# inktime.net
KiCad netlist of a schematic drawn in EAGLE
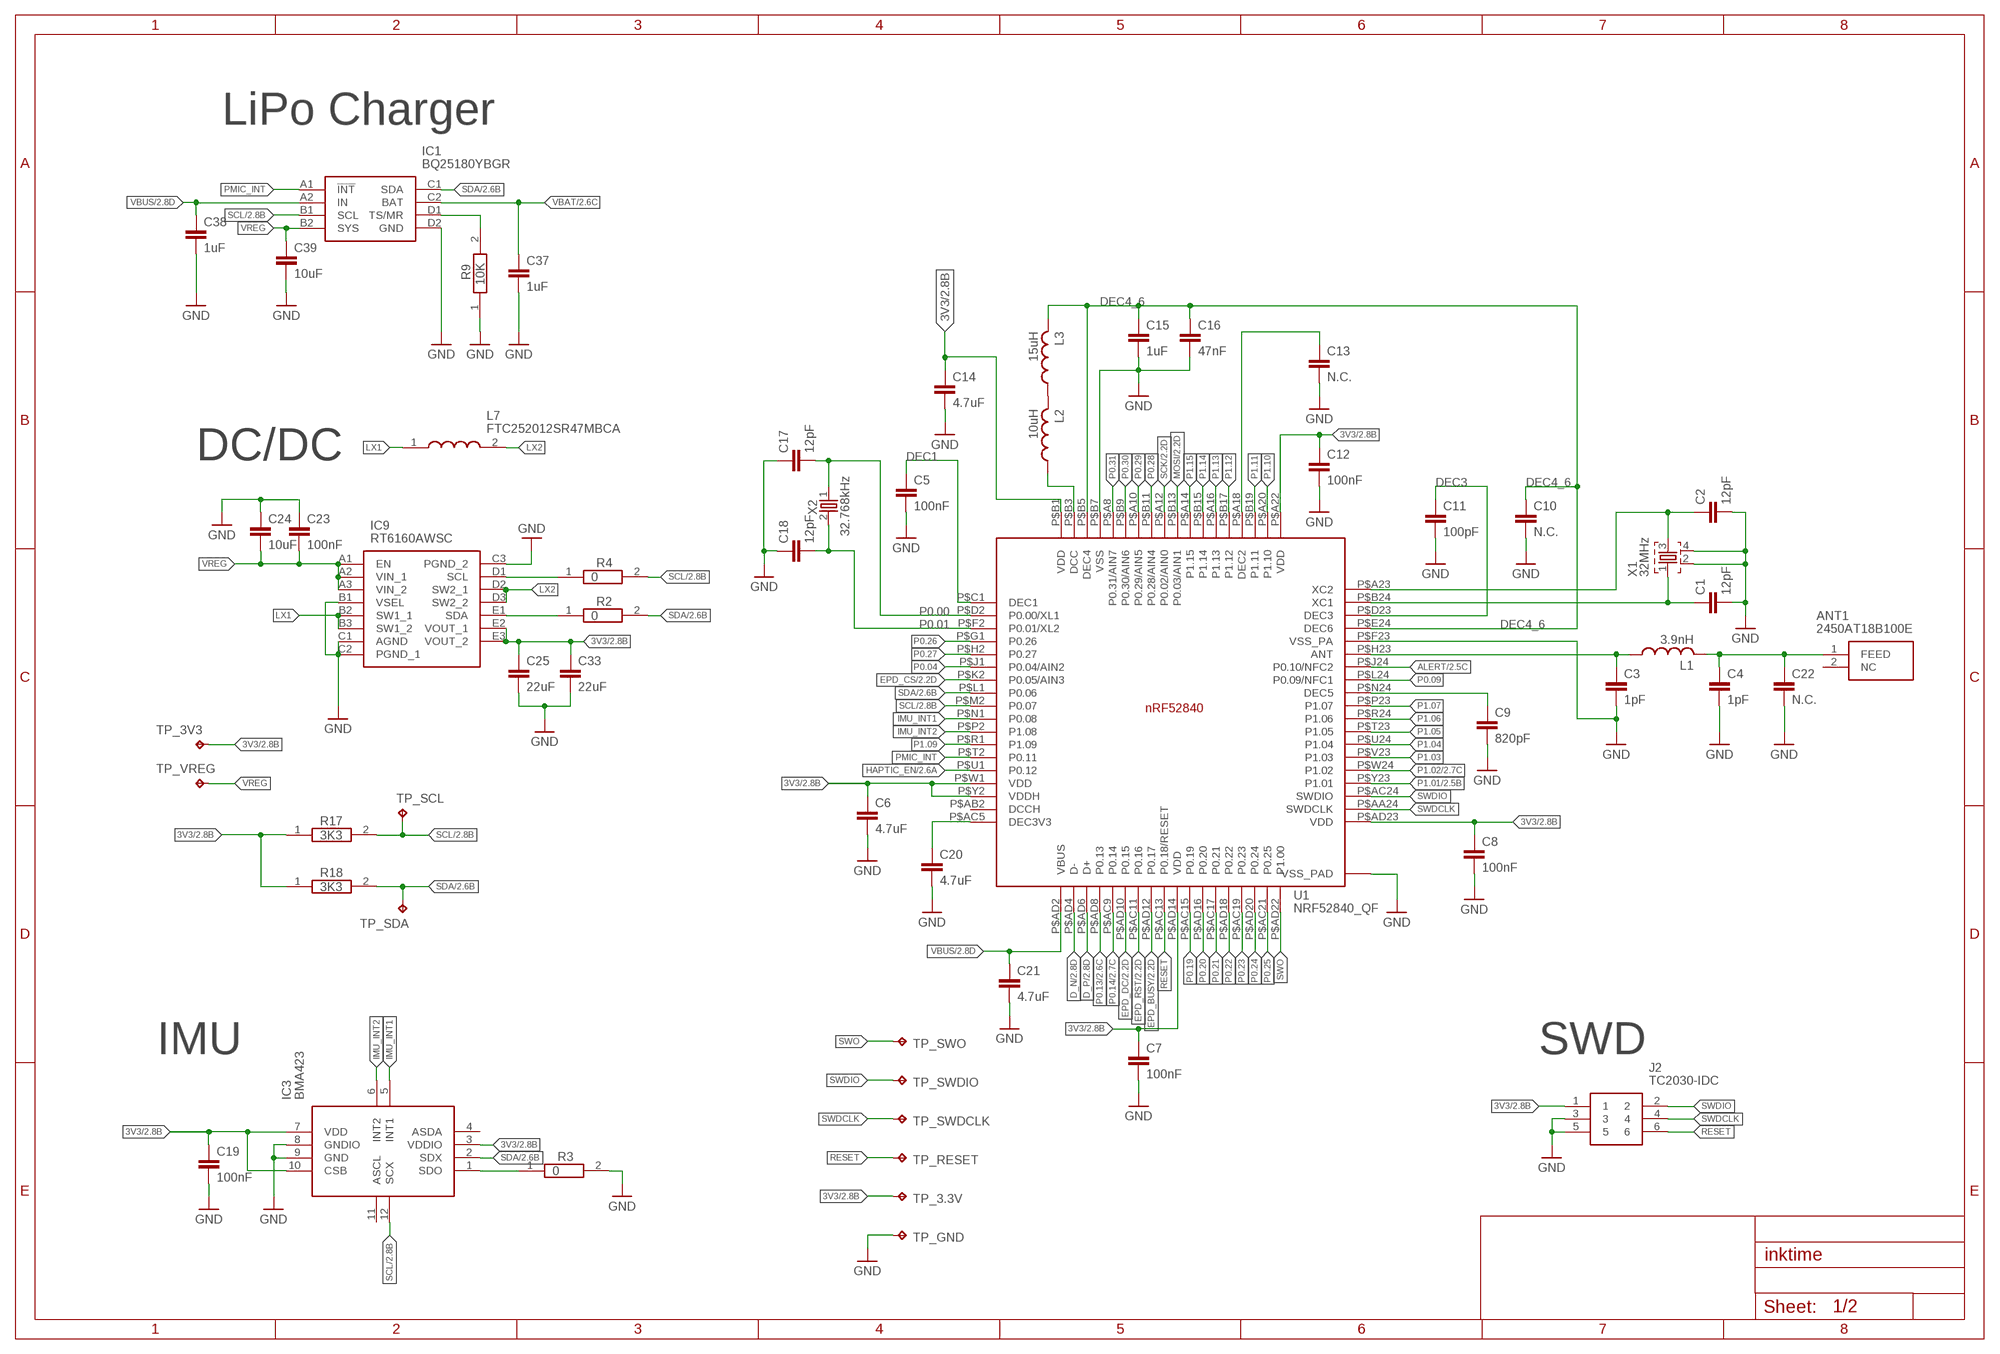
[diagram p0: schematic, sheet 1]
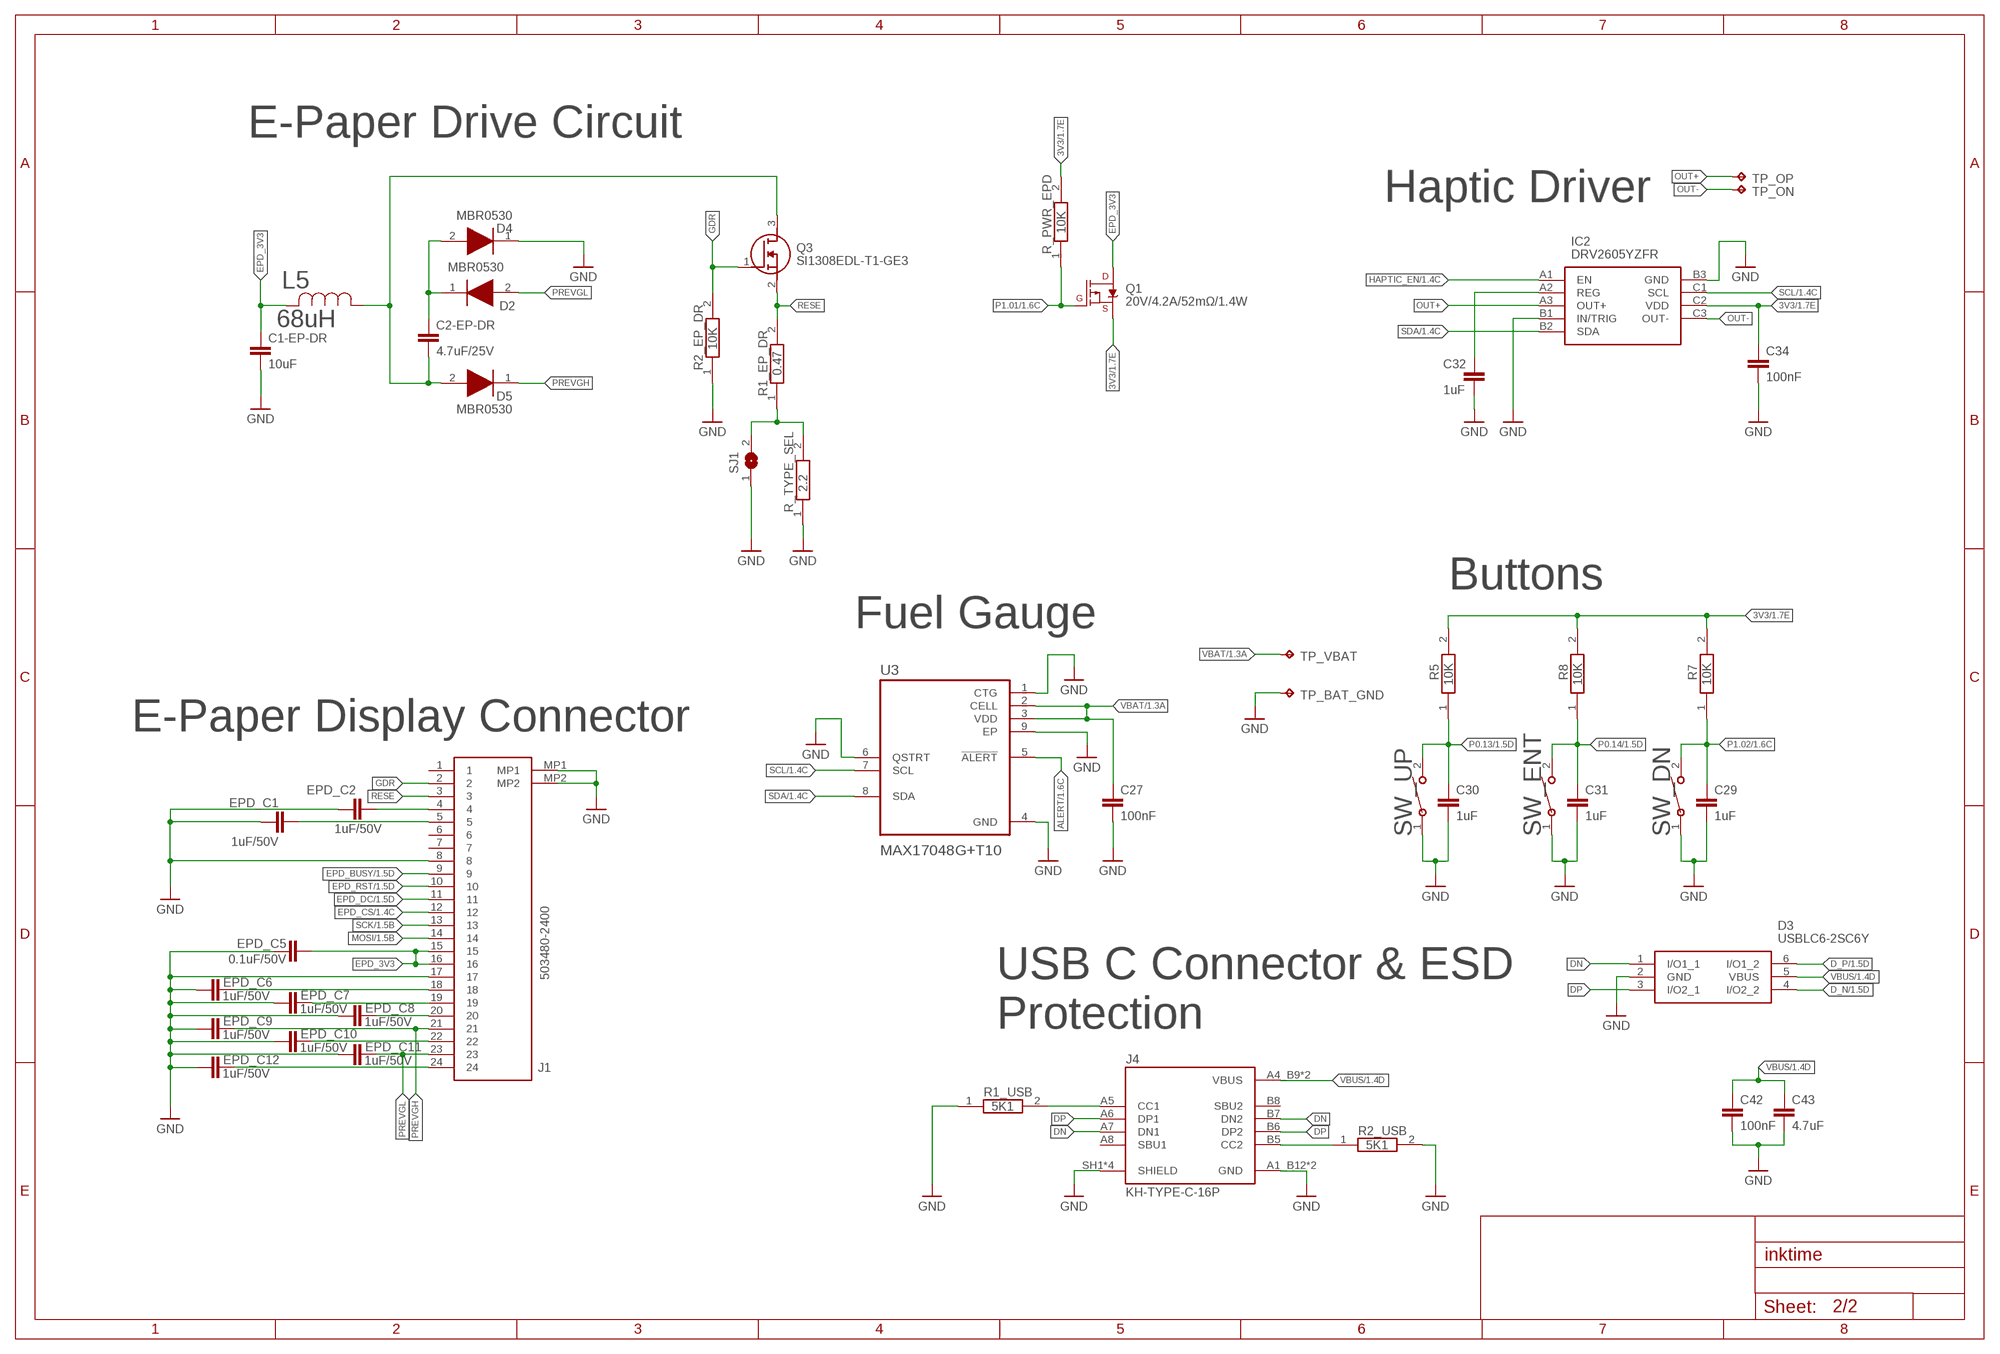
[diagram p1: schematic, sheet 2]

(export (version "E")
  (design (tool "Eeschema 10.0.6"))
  (components
    (comp (ref "C1-EP-DR")
      (value "10uF")
      (footprint "eagle-import:NORDIC_NRF_3_RESC0402_L")
      (libsource (lib "eagle-import") (part "NORDIC_NRF_3_CAPACITOR_0402_L"))
    )
    (comp (ref "C2-EP-DR")
      (value "4.7uF/25V")
      (footprint "eagle-import:NORDIC_NRF_3_RESC0402_L")
      (libsource (lib "eagle-import") (part "NORDIC_NRF_3_CAPACITOR_0402_L"))
    )
    (comp (ref "C27")
      (value "100nF")
      (footprint "eagle-import:NORDIC_NRF_3_RESC0201_L")
      (libsource (lib "eagle-import") (part "NORDIC_NRF_3_CAPACITOR_0201_L"))
    )
    (comp (ref "C29")
      (value "1uF")
      (footprint "eagle-import:NORDIC_NRF_3_RESC0402_L")
      (libsource (lib "eagle-import") (part "NORDIC_NRF_3_CAPACITOR_0402_L"))
    )
    (comp (ref "C30")
      (value "1uF")
      (footprint "eagle-import:NORDIC_NRF_3_RESC0402_L")
      (libsource (lib "eagle-import") (part "NORDIC_NRF_3_CAPACITOR_0402_L"))
    )
    (comp (ref "C31")
      (value "1uF")
      (footprint "eagle-import:NORDIC_NRF_3_RESC0402_L")
      (libsource (lib "eagle-import") (part "NORDIC_NRF_3_CAPACITOR_0402_L"))
    )
    (comp (ref "C32")
      (value "1uF")
      (footprint "eagle-import:NORDIC_NRF_3_RESC0402_L")
      (libsource (lib "eagle-import") (part "NORDIC_NRF_3_CAPACITOR_0402_L"))
    )
    (comp (ref "C34")
      (value "100nF")
      (footprint "eagle-import:NORDIC_NRF_3_RESC0201_L")
      (libsource (lib "eagle-import") (part "NORDIC_NRF_3_CAPACITOR_0201_L"))
    )
    (comp (ref "C42")
      (value "100nF")
      (footprint "eagle-import:NORDIC_NRF_3_RESC0201_L")
      (libsource (lib "eagle-import") (part "NORDIC_NRF_3_CAPACITOR_0201_L"))
    )
    (comp (ref "C43")
      (value "4.7uF")
      (footprint "eagle-import:NORDIC_NRF_3_RESC0402_L")
      (libsource (lib "eagle-import") (part "NORDIC_NRF_3_CAPACITOR_0402_L"))
    )
    (comp (ref "D2")
      (value "MBR0530")
      (footprint "eagle-import:ESP32_C6_LIBRARY_5_SOD3716X135N")
      (libsource (lib "eagle-import") (part "ESP32_C6_LIBRARY_5_MBR0530SOD"))
    )
    (comp (ref "D3")
      (value "USBLC6-2SC6Y")
      (footprint "eagle-import:ESP32_C6_LIBRARY_3_SOT95P280X145-6N")
      (fields (field (name "MF") "STMicroelectronics"))
      (libsource (lib "eagle-import") (part "ESP32_C6_LIBRARY_3_USBLC6-2SC6Y"))
    )
    (comp (ref "D4")
      (value "MBR0530")
      (footprint "eagle-import:ESP32_C6_LIBRARY_5_SOD3716X135N")
      (libsource (lib "eagle-import") (part "ESP32_C6_LIBRARY_5_MBR0530SOD"))
    )
    (comp (ref "D5")
      (value "MBR0530")
      (footprint "eagle-import:ESP32_C6_LIBRARY_5_SOD3716X135N")
      (libsource (lib "eagle-import") (part "ESP32_C6_LIBRARY_5_MBR0530SOD"))
    )
    (comp (ref "EPD_C1")
      (value "1uF/50V")
      (footprint "eagle-import:NORDIC_NRF_3_RESC0402_L")
      (libsource (lib "eagle-import") (part "NORDIC_NRF_3_CAPACITOR_0402_L"))
    )
    (comp (ref "EPD_C2")
      (value "1uF/50V")
      (footprint "eagle-import:NORDIC_NRF_3_RESC0402_L")
      (libsource (lib "eagle-import") (part "NORDIC_NRF_3_CAPACITOR_0402_L"))
    )
    (comp (ref "EPD_C5")
      (value "0.1uF/50V")
      (footprint "eagle-import:NORDIC_NRF_3_RESC0201_L")
      (libsource (lib "eagle-import") (part "NORDIC_NRF_3_CAPACITOR_0201_L"))
    )
    (comp (ref "EPD_C6")
      (value "1uF/50V")
      (footprint "eagle-import:NORDIC_NRF_3_RESC0402_L")
      (libsource (lib "eagle-import") (part "NORDIC_NRF_3_CAPACITOR_0402_L"))
    )
    (comp (ref "EPD_C7")
      (value "1uF/50V")
      (footprint "eagle-import:NORDIC_NRF_3_RESC0402_L")
      (libsource (lib "eagle-import") (part "NORDIC_NRF_3_CAPACITOR_0402_L"))
    )
    (comp (ref "EPD_C8")
      (value "1uF/50V")
      (footprint "eagle-import:NORDIC_NRF_3_RESC0402_L")
      (libsource (lib "eagle-import") (part "NORDIC_NRF_3_CAPACITOR_0402_L"))
    )
    (comp (ref "EPD_C9")
      (value "1uF/50V")
      (footprint "eagle-import:NORDIC_NRF_3_RESC0402_L")
      (libsource (lib "eagle-import") (part "NORDIC_NRF_3_CAPACITOR_0402_L"))
    )
    (comp (ref "EPD_C10")
      (value "1uF/50V")
      (footprint "eagle-import:NORDIC_NRF_3_RESC0402_L")
      (libsource (lib "eagle-import") (part "NORDIC_NRF_3_CAPACITOR_0402_L"))
    )
    (comp (ref "EPD_C11")
      (value "1uF/50V")
      (footprint "eagle-import:NORDIC_NRF_3_RESC0402_L")
      (libsource (lib "eagle-import") (part "NORDIC_NRF_3_CAPACITOR_0402_L"))
    )
    (comp (ref "EPD_C12")
      (value "1uF/50V")
      (footprint "eagle-import:NORDIC_NRF_3_RESC0402_L")
      (libsource (lib "eagle-import") (part "NORDIC_NRF_3_CAPACITOR_0402_L"))
    )
    (comp (ref "IC2")
      (value "DRV2605YZFR")
      (footprint "eagle-import:DRV2605YZFR_BGA9C50P3X3_144X144X62")
      (libsource (lib "eagle-import") (part "DRV2605YZFR_DRV2605YZFR"))
    )
    (comp (ref "J1")
      (value "503480-2400")
      (footprint "eagle-import:503480-2400_5034802400")
      (fields (field (name "MOUSER_PART_NUMBER") "538-503480-2400"))
      (libsource (lib "eagle-import") (part "503480-2400_503480-2400"))
    )
    (comp (ref "J4")
      (value "KH-TYPE-C-16P")
      (footprint "eagle-import:KH-TYPE-C-16P_KINGHELM_KH-TYPE-C-16P")
      (fields (field (name "MF") "kinghelm"))
      (libsource (lib "eagle-import") (part "KH-TYPE-C-16P_KH-TYPE-C-16P"))
    )
    (comp (ref "L5")
      (value "68uH")
      (footprint "eagle-import:ESP32_C6_LIBRARY_2_IND_4828-WE-TPC_WRE")
      (fields
        (field (name "MANUFACTURER_PART_NUMBER") "744043680")
        (field (name "COPYRIGHT") "Copyright (C) 2024 Ultra Librarian. All rights reserved.")
      )
      (libsource (lib "eagle-import") (part "ESP32_C6_LIBRARY_2_744043680IND_4828-WE-TPC_WRE"))
    )
    (comp (ref "Q1")
      (value "20V/4.2A/52mΩ/1.4W")
      (footprint "eagle-import:ESP32_C6_LIBRARY_4_ESP32_C6_LIBRARY_4_ESP32_C6_LIBRARY_4_ESP32_C6_LIBRARY_4_ESP32_WROVER_SPARKFUN-DISCRETESEMI_SOT23-3")
      (libsource (lib "eagle-import") (part "ESP32_C6_LIBRARY_4_ESP32_WROVER_SPARKFUN-DISCRETESEMI_MOSFET_PCH-DMG2305UX-7"))
    )
    (comp (ref "Q3")
      (value "SI1308EDL-T1-GE3")
      (footprint "eagle-import:ESP32_C6_LIBRARY_6_SOT65P210X110-3N")
      (fields (field (name "MF") "Vishay Siliconix"))
      (libsource (lib "eagle-import") (part "ESP32_C6_LIBRARY_6_SI1308EDL-T1-GE3"))
    )
    (comp (ref "R1_EP_DR")
      (value "0.47")
      (footprint "eagle-import:CPF0201D7K68C1_0201")
      (libsource (lib "eagle-import") (part "CPF0201D7K68C1_CPF0201D7K68C1"))
    )
    (comp (ref "R1_USB")
      (value "5K1")
      (footprint "eagle-import:CPF0201D7K68C1_0201")
      (libsource (lib "eagle-import") (part "CPF0201D7K68C1_CPF0201D7K68C1"))
    )
    (comp (ref "R2_EP_DR")
      (value "10K")
      (footprint "eagle-import:CPF0201D7K68C1_0201")
      (libsource (lib "eagle-import") (part "CPF0201D7K68C1_CPF0201D7K68C1"))
    )
    (comp (ref "R2_USB")
      (value "5K1")
      (footprint "eagle-import:CPF0201D7K68C1_0201")
      (libsource (lib "eagle-import") (part "CPF0201D7K68C1_CPF0201D7K68C1"))
    )
    (comp (ref "R5")
      (value "10K")
      (footprint "eagle-import:CPF0201D7K68C1_0201")
      (libsource (lib "eagle-import") (part "CPF0201D7K68C1_CPF0201D7K68C1"))
    )
    (comp (ref "R7")
      (value "10K")
      (footprint "eagle-import:CPF0201D7K68C1_0201")
      (libsource (lib "eagle-import") (part "CPF0201D7K68C1_CPF0201D7K68C1"))
    )
    (comp (ref "R8")
      (value "10K")
      (footprint "eagle-import:CPF0201D7K68C1_0201")
      (libsource (lib "eagle-import") (part "CPF0201D7K68C1_CPF0201D7K68C1"))
    )
    (comp (ref "R_PWR_EPD")
      (value "10K")
      (footprint "eagle-import:CPF0201D7K68C1_0201")
      (libsource (lib "eagle-import") (part "CPF0201D7K68C1_CPF0201D7K68C1"))
    )
    (comp (ref "R_TYPE_SEL")
      (value "2.2")
      (footprint "eagle-import:CPF0201D7K68C1_0201")
      (libsource (lib "eagle-import") (part "CPF0201D7K68C1_CPF0201D7K68C1"))
    )
    (comp (ref "SJ1")
      (value "ESP32_C6_LIBRARY_7_JUMPER_SJ")
      (footprint "eagle-import:ESP32_C6_LIBRARY_7_JUMPER_SJ")
      (libsource (lib "eagle-import") (part "ESP32_C6_LIBRARY_7_JUMPER_SJ"))
    )
    (comp (ref "SW_DN")
      (value "2025-10-22_07-23-44_LIBRARY_EVP-AKE31ASW_EVP-AKE31A_PAN")
      (footprint "eagle-import:2025-10-22_07-23-44_LIBRARY_SW_EVP-AKE31A_PAN")
      (fields
        (field (name "MANUFACTURER_PART_NUMBER") "EVP-AKE31A")
        (field (name "COPYRIGHT") "Copyright (C) 2025 Ultra Librarian. All rights reserved.")
      )
      (libsource (lib "eagle-import") (part "2025-10-22_07-23-44_LIBRARY_EVP-AKE31ASW_EVP-AKE31A_PAN"))
    )
    (comp (ref "SW_ENT")
      (value "2025-10-22_07-23-44_LIBRARY_EVP-AKE31ASW_EVP-AKE31A_PAN")
      (footprint "eagle-import:2025-10-22_07-23-44_LIBRARY_SW_EVP-AKE31A_PAN")
      (fields
        (field (name "MANUFACTURER_PART_NUMBER") "EVP-AKE31A")
        (field (name "COPYRIGHT") "Copyright (C) 2025 Ultra Librarian. All rights reserved.")
      )
      (libsource (lib "eagle-import") (part "2025-10-22_07-23-44_LIBRARY_EVP-AKE31ASW_EVP-AKE31A_PAN"))
    )
    (comp (ref "SW_UP")
      (value "2025-10-22_07-23-44_LIBRARY_EVP-AKE31ASW_EVP-AKE31A_PAN")
      (footprint "eagle-import:2025-10-22_07-23-44_LIBRARY_SW_EVP-AKE31A_PAN")
      (fields
        (field (name "MANUFACTURER_PART_NUMBER") "EVP-AKE31A")
        (field (name "COPYRIGHT") "Copyright (C) 2025 Ultra Librarian. All rights reserved.")
      )
      (libsource (lib "eagle-import") (part "2025-10-22_07-23-44_LIBRARY_EVP-AKE31ASW_EVP-AKE31A_PAN"))
    )
    (comp (ref "TP_BAT_GND")
      (value "HECTOR_WATCH_1_TPTP20R")
      (footprint "eagle-import:HECTOR_WATCH_1_TP20R")
      (libsource (lib "eagle-import") (part "HECTOR_WATCH_1_TPTP20R"))
    )
    (comp (ref "TP_ON")
      (value "HECTOR_WATCH_1_TPTP20R")
      (footprint "eagle-import:HECTOR_WATCH_1_TP20R")
      (libsource (lib "eagle-import") (part "HECTOR_WATCH_1_TPTP20R"))
    )
    (comp (ref "TP_OP")
      (value "HECTOR_WATCH_1_TPTP20R")
      (footprint "eagle-import:HECTOR_WATCH_1_TP20R")
      (libsource (lib "eagle-import") (part "HECTOR_WATCH_1_TPTP20R"))
    )
    (comp (ref "TP_VBAT")
      (value "HECTOR_WATCH_1_TPTP20R")
      (footprint "eagle-import:HECTOR_WATCH_1_TP20R")
      (libsource (lib "eagle-import") (part "HECTOR_WATCH_1_TPTP20R"))
    )
    (comp (ref "U3")
      (value "MAX17048G+T10")
      (footprint "eagle-import:ESP32_C6_LIBRARY_SON50P200X200X80-9N")
      (fields (field (name "MF") "Analog Devices"))
      (libsource (lib "eagle-import") (part "ESP32_C6_LIBRARY_MAX17048G+T10"))
    )
    (comp (ref "ANT1")
      (value "2450AT18B100E")
      (footprint "eagle-import:2450AT18B100E_ANTC3216X140N")
      (fields (field (name "MOUSER_PART_NUMBER") "609-2450AT18B100E"))
      (libsource (lib "eagle-import") (part "2450AT18B100E_2450AT18B100E"))
    )
    (comp (ref "C1")
      (value "12pF")
      (footprint "eagle-import:NORDIC_NRF_3_RESC0201_L")
      (libsource (lib "eagle-import") (part "NORDIC_NRF_3_CAPACITOR_0201_L"))
    )
    (comp (ref "C2")
      (value "12pF")
      (footprint "eagle-import:NORDIC_NRF_3_RESC0201_L")
      (libsource (lib "eagle-import") (part "NORDIC_NRF_3_CAPACITOR_0201_L"))
    )
    (comp (ref "C3")
      (value "1pF")
      (footprint "eagle-import:NORDIC_NRF_3_RESC0201_L")
      (libsource (lib "eagle-import") (part "NORDIC_NRF_3_CAPACITOR_0201_L"))
    )
    (comp (ref "C4")
      (value "1pF")
      (footprint "eagle-import:NORDIC_NRF_3_RESC0201_L")
      (libsource (lib "eagle-import") (part "NORDIC_NRF_3_CAPACITOR_0201_L"))
    )
    (comp (ref "C5")
      (value "100nF")
      (footprint "eagle-import:NORDIC_NRF_3_RESC0201_L")
      (libsource (lib "eagle-import") (part "NORDIC_NRF_3_CAPACITOR_0201_L"))
    )
    (comp (ref "C6")
      (value "4.7uF")
      (footprint "eagle-import:NORDIC_NRF_3_RESC0402_L")
      (libsource (lib "eagle-import") (part "NORDIC_NRF_3_CAPACITOR_0402_L"))
    )
    (comp (ref "C7")
      (value "100nF")
      (footprint "eagle-import:NORDIC_NRF_3_RESC0201_L")
      (libsource (lib "eagle-import") (part "NORDIC_NRF_3_CAPACITOR_0201_L"))
    )
    (comp (ref "C8")
      (value "100nF")
      (footprint "eagle-import:NORDIC_NRF_3_RESC0201_L")
      (libsource (lib "eagle-import") (part "NORDIC_NRF_3_CAPACITOR_0201_L"))
    )
    (comp (ref "C9")
      (value "820pF")
      (footprint "eagle-import:NORDIC_NRF_3_RESC0201_L")
      (libsource (lib "eagle-import") (part "NORDIC_NRF_3_CAPACITOR_0201_L"))
    )
    (comp (ref "C10")
      (value "N.C.")
      (footprint "eagle-import:NORDIC_NRF_3_RESC0201_L")
      (libsource (lib "eagle-import") (part "NORDIC_NRF_3_CAPACITOR_0201_L"))
    )
    (comp (ref "C11")
      (value "100pF")
      (footprint "eagle-import:NORDIC_NRF_3_RESC0201_L")
      (libsource (lib "eagle-import") (part "NORDIC_NRF_3_CAPACITOR_0201_L"))
    )
    (comp (ref "C12")
      (value "100nF")
      (footprint "eagle-import:NORDIC_NRF_3_RESC0201_L")
      (libsource (lib "eagle-import") (part "NORDIC_NRF_3_CAPACITOR_0201_L"))
    )
    (comp (ref "C13")
      (value "N.C.")
      (footprint "eagle-import:NORDIC_NRF_3_RESC0201_L")
      (libsource (lib "eagle-import") (part "NORDIC_NRF_3_CAPACITOR_0201_L"))
    )
    (comp (ref "C14")
      (value "4.7uF")
      (footprint "eagle-import:NORDIC_NRF_3_RESC0402_L")
      (libsource (lib "eagle-import") (part "NORDIC_NRF_3_CAPACITOR_0402_L"))
    )
    (comp (ref "C15")
      (value "1uF")
      (footprint "eagle-import:NORDIC_NRF_3_RESC0402_L")
      (libsource (lib "eagle-import") (part "NORDIC_NRF_3_CAPACITOR_0402_L"))
    )
    (comp (ref "C16")
      (value "47nF")
      (footprint "eagle-import:NORDIC_NRF_3_RESC0201_L")
      (libsource (lib "eagle-import") (part "NORDIC_NRF_3_CAPACITOR_0201_L"))
    )
    (comp (ref "C17")
      (value "12pF")
      (footprint "eagle-import:NORDIC_NRF_3_RESC0201_L")
      (libsource (lib "eagle-import") (part "NORDIC_NRF_3_CAPACITOR_0201_L"))
    )
    (comp (ref "C18")
      (value "12pF")
      (footprint "eagle-import:NORDIC_NRF_3_RESC0201_L")
      (libsource (lib "eagle-import") (part "NORDIC_NRF_3_CAPACITOR_0201_L"))
    )
    (comp (ref "C19")
      (value "100nF")
      (footprint "eagle-import:NORDIC_NRF_3_RESC0201_L")
      (libsource (lib "eagle-import") (part "NORDIC_NRF_3_CAPACITOR_0201_L"))
    )
    (comp (ref "C20")
      (value "4.7uF")
      (footprint "eagle-import:NORDIC_NRF_3_RESC0402_L")
      (libsource (lib "eagle-import") (part "NORDIC_NRF_3_CAPACITOR_0402_L"))
    )
    (comp (ref "C21")
      (value "4.7uF")
      (footprint "eagle-import:NORDIC_NRF_3_RESC0402_L")
      (libsource (lib "eagle-import") (part "NORDIC_NRF_3_CAPACITOR_0402_L"))
    )
    (comp (ref "C22")
      (value "N.C.")
      (footprint "eagle-import:NORDIC_NRF_3_RESC0201_L")
      (libsource (lib "eagle-import") (part "NORDIC_NRF_3_CAPACITOR_0201_L"))
    )
    (comp (ref "C23")
      (value "100nF")
      (footprint "eagle-import:NORDIC_NRF_3_RESC0201_L")
      (libsource (lib "eagle-import") (part "NORDIC_NRF_3_CAPACITOR_0201_L"))
    )
    (comp (ref "C24")
      (value "10uF")
      (footprint "eagle-import:NORDIC_NRF_3_RESC0402_L")
      (libsource (lib "eagle-import") (part "NORDIC_NRF_3_CAPACITOR_0402_L"))
    )
    (comp (ref "C25")
      (value "22uF")
      (footprint "eagle-import:NORDIC_NRF_3_RESC0402_L")
      (libsource (lib "eagle-import") (part "NORDIC_NRF_3_CAPACITOR_0402_L"))
    )
    (comp (ref "C33")
      (value "22uF")
      (footprint "eagle-import:NORDIC_NRF_3_RESC0402_L")
      (libsource (lib "eagle-import") (part "NORDIC_NRF_3_CAPACITOR_0402_L"))
    )
    (comp (ref "C37")
      (value "1uF")
      (footprint "eagle-import:NORDIC_NRF_3_RESC0402_L")
      (libsource (lib "eagle-import") (part "NORDIC_NRF_3_CAPACITOR_0402_L"))
    )
    (comp (ref "C38")
      (value "1uF")
      (footprint "eagle-import:NORDIC_NRF_3_RESC0402_L")
      (libsource (lib "eagle-import") (part "NORDIC_NRF_3_CAPACITOR_0402_L"))
    )
    (comp (ref "C39")
      (value "10uF")
      (footprint "eagle-import:NORDIC_NRF_3_RESC0402_L")
      (libsource (lib "eagle-import") (part "NORDIC_NRF_3_CAPACITOR_0402_L"))
    )
    (comp (ref "IC1")
      (value "BQ25180YBGR")
      (footprint "eagle-import:BQ25180YBGR_BGA8C40P2X4_100X155X50")
      (fields (field (name "MOUSER_PART_NUMBER") "595-BQ25180YBGR"))
      (libsource (lib "eagle-import") (part "BQ25180YBGR_BQ25180YBGR"))
    )
    (comp (ref "IC3")
      (value "BMA423")
      (footprint "eagle-import:BMA423_BMA423")
      (fields (field (name "MOUSER_PART_NUMBER") "262-BMA423"))
      (libsource (lib "eagle-import") (part "BMA423_BMA423"))
    )
    (comp (ref "IC9")
      (value "RT6160AWSC")
      (footprint "eagle-import:RT6160AWSC_BGA15C40P3X5_140X230X60")
      (fields (field (name "MOUSER_PART_NUMBER") "835-RT6160AWSC"))
      (libsource (lib "eagle-import") (part "RT6160AWSC_RT6160AWSC"))
    )
    (comp (ref "J2")
      (value "TC2030-IDC")
      (footprint "eagle-import:TC2030-IDC_TC2030IDC")
      (libsource (lib "eagle-import") (part "TC2030-IDC_TC2030-IDC"))
    )
    (comp (ref "L1")
      (value "3.9nH")
      (footprint "eagle-import:NORDIC_NRF_2_RESC0402_L")
      (libsource (lib "eagle-import") (part "NORDIC_NRF_2_INDUCTOR_0402_L"))
    )
    (comp (ref "L2")
      (value "10uH")
      (footprint "eagle-import:NORDIC_NRF_2_RESC0402_L")
      (libsource (lib "eagle-import") (part "NORDIC_NRF_2_INDUCTOR_0402_L"))
    )
    (comp (ref "L3")
      (value "15uH")
      (footprint "eagle-import:NORDIC_NRF_2_RESC0402_L")
      (libsource (lib "eagle-import") (part "NORDIC_NRF_2_INDUCTOR_0402_L"))
    )
    (comp (ref "L7")
      (value "FTC252012SR47MBCA")
      (footprint "eagle-import:MLP2016SR47MT0S1_INDC2016X100N")
      (libsource (lib "eagle-import") (part "MLP2016SR47MT0S1_FTC252012SR47MBCA"))
    )
    (comp (ref "R2")
      (value "0")
      (footprint "eagle-import:CPF0201D7K68C1_0201")
      (libsource (lib "eagle-import") (part "CPF0201D7K68C1_CPF0201D7K68C1"))
    )
    (comp (ref "R3")
      (value "0")
      (footprint "eagle-import:CPF0201D7K68C1_0201")
      (libsource (lib "eagle-import") (part "CPF0201D7K68C1_CPF0201D7K68C1"))
    )
    (comp (ref "R4")
      (value "0")
      (footprint "eagle-import:CPF0201D7K68C1_0201")
      (libsource (lib "eagle-import") (part "CPF0201D7K68C1_CPF0201D7K68C1"))
    )
    (comp (ref "R9")
      (value "10K")
      (footprint "eagle-import:CPF0201D7K68C1_0201")
      (libsource (lib "eagle-import") (part "CPF0201D7K68C1_CPF0201D7K68C1"))
    )
    (comp (ref "R17")
      (value "3K3")
      (footprint "eagle-import:CPF0201D7K68C1_0201")
      (libsource (lib "eagle-import") (part "CPF0201D7K68C1_CPF0201D7K68C1"))
    )
    (comp (ref "R18")
      (value "3K3")
      (footprint "eagle-import:CPF0201D7K68C1_0201")
      (libsource (lib "eagle-import") (part "CPF0201D7K68C1_CPF0201D7K68C1"))
    )
    (comp (ref "TP_3.3V")
      (value "HECTOR_WATCH_1_TPTP20R")
      (footprint "eagle-import:HECTOR_WATCH_1_TP20R")
      (libsource (lib "eagle-import") (part "HECTOR_WATCH_1_TPTP20R"))
    )
    (comp (ref "TP_3V3")
      (value "HECTOR_WATCH_1_TPTP20R")
      (footprint "eagle-import:HECTOR_WATCH_1_TP20R")
      (libsource (lib "eagle-import") (part "HECTOR_WATCH_1_TPTP20R"))
    )
    (comp (ref "TP_GND")
      (value "HECTOR_WATCH_1_TPTP20R")
      (footprint "eagle-import:HECTOR_WATCH_1_TP20R")
      (libsource (lib "eagle-import") (part "HECTOR_WATCH_1_TPTP20R"))
    )
    (comp (ref "TP_RESET")
      (value "HECTOR_WATCH_1_TPTP20R")
      (footprint "eagle-import:HECTOR_WATCH_1_TP20R")
      (libsource (lib "eagle-import") (part "HECTOR_WATCH_1_TPTP20R"))
    )
    (comp (ref "TP_SCL")
      (value "HECTOR_WATCH_1_TPTP20R")
      (footprint "eagle-import:HECTOR_WATCH_1_TP20R")
      (libsource (lib "eagle-import") (part "HECTOR_WATCH_1_TPTP20R"))
    )
    (comp (ref "TP_SDA")
      (value "HECTOR_WATCH_1_TPTP20R")
      (footprint "eagle-import:HECTOR_WATCH_1_TP20R")
      (libsource (lib "eagle-import") (part "HECTOR_WATCH_1_TPTP20R"))
    )
    (comp (ref "TP_SWDCLK")
      (value "HECTOR_WATCH_1_TPTP20R")
      (footprint "eagle-import:HECTOR_WATCH_1_TP20R")
      (libsource (lib "eagle-import") (part "HECTOR_WATCH_1_TPTP20R"))
    )
    (comp (ref "TP_SWDIO")
      (value "HECTOR_WATCH_1_TPTP20R")
      (footprint "eagle-import:HECTOR_WATCH_1_TP20R")
      (libsource (lib "eagle-import") (part "HECTOR_WATCH_1_TPTP20R"))
    )
    (comp (ref "TP_SWO")
      (value "HECTOR_WATCH_1_TPTP20R")
      (footprint "eagle-import:HECTOR_WATCH_1_TP20R")
      (libsource (lib "eagle-import") (part "HECTOR_WATCH_1_TPTP20R"))
    )
    (comp (ref "TP_VREG")
      (value "HECTOR_WATCH_1_TPTP20R")
      (footprint "eagle-import:HECTOR_WATCH_1_TP20R")
      (libsource (lib "eagle-import") (part "HECTOR_WATCH_1_TPTP20R"))
    )
    (comp (ref "U1")
      (value "NRF52840_QF")
      (footprint "eagle-import:NORDIC_NRF_4_AQFN50P700X700X85_HS-74N")
      (libsource (lib "eagle-import") (part "NORDIC_NRF_4_NRF52840_QF"))
    )
    (comp (ref "X1")
      (value "32MHz")
      (footprint "eagle-import:NORDIC_NRF_BT-XTAL_2016_N")
      (libsource (lib "eagle-import") (part "NORDIC_NRF_XTAL_32MHZ"))
    )
    (comp (ref "X2")
      (value "32.768kHz")
      (footprint "eagle-import:NORDIC_NRF_1_XTAL_3215_N")
      (libsource (lib "eagle-import") (part "NORDIC_NRF_1_XTAL_32KHZ"))
    )
  )
  (nets
    (net (code "1") (name "3V3") (class "Default")
      (node (ref "C12") (pin "1") (pinfunction "1_1") (pintype "passive"))
      (node (ref "C14") (pin "1") (pinfunction "1_1") (pintype "passive"))
      (node (ref "C19") (pin "1") (pinfunction "1_1") (pintype "passive"))
      (node (ref "C25") (pin "1") (pinfunction "1_1") (pintype "passive"))
      (node (ref "C33") (pin "1") (pinfunction "1_1") (pintype "passive"))
      (node (ref "C34") (pin "1") (pinfunction "1_1") (pintype "passive"))
      (node (ref "C6") (pin "1") (pinfunction "1_1") (pintype "passive"))
      (node (ref "C7") (pin "1") (pinfunction "1_1") (pintype "passive"))
      (node (ref "C8") (pin "1") (pinfunction "1_1") (pintype "passive"))
      (node (ref "IC2") (pin "C2") (pinfunction "VDD_C2") (pintype "bidirectional"))
      (node (ref "IC3") (pin "10") (pinfunction "CSB_10") (pintype "bidirectional"))
      (node (ref "IC3") (pin "3") (pinfunction "VDDIO_3") (pintype "bidirectional"))
      (node (ref "IC3") (pin "7") (pinfunction "VDD_7") (pintype "bidirectional"))
      (node (ref "IC9") (pin "E2") (pinfunction "VOUT_1_E2") (pintype "bidirectional"))
      (node (ref "IC9") (pin "E3") (pinfunction "VOUT_2_E3") (pintype "bidirectional"))
      (node (ref "J2") (pin "1") (pinfunction "1_1") (pintype "bidirectional"))
      (node (ref "Q1") (pin "2") (pinfunction "S_2") (pintype "bidirectional"))
      (node (ref "R17") (pin "1") (pinfunction "1_1") (pintype "bidirectional"))
      (node (ref "R18") (pin "1") (pinfunction "1_1") (pintype "bidirectional"))
      (node (ref "R5") (pin "2") (pinfunction "2_2") (pintype "bidirectional"))
      (node (ref "R7") (pin "2") (pinfunction "2_2") (pintype "bidirectional"))
      (node (ref "R8") (pin "2") (pinfunction "2_2") (pintype "bidirectional"))
      (node (ref "R_PWR_EPD") (pin "2") (pinfunction "2_2") (pintype "bidirectional"))
      (node (ref "TP_3.3V") (pin "TP") (pinfunction "TP_TP") (pintype "input"))
      (node (ref "TP_3V3") (pin "TP") (pinfunction "TP_TP") (pintype "input"))
      (node (ref "U1") (pin "P$A22") (pinfunction "VDD_P$A22") (pintype "power_in"))
      (node (ref "U1") (pin "P$AD14") (pinfunction "VDD_P$AD14") (pintype "power_in"))
      (node (ref "U1") (pin "P$AD23") (pinfunction "VDD_P$AD23") (pintype "power_in"))
      (node (ref "U1") (pin "P$B1") (pinfunction "VDD_P$B1") (pintype "power_in"))
      (node (ref "U1") (pin "P$W1") (pinfunction "VDD_P$W1") (pintype "power_in"))
      (node (ref "U1") (pin "P$Y2") (pinfunction "VDDH_P$Y2") (pintype "power_in"))
    )
    (net (code "2") (name "ALERT") (class "Default")
      (node (ref "U1") (pin "P$J24") (pinfunction "P0.10/NFC2_P$J24") (pintype "bidirectional"))
      (node (ref "U3") (pin "5") (pinfunction "~{ALERT}_5") (pintype "output"))
    )
    (net (code "3") (name "DEC1") (class "Default")
      (node (ref "C5") (pin "1") (pinfunction "1_1") (pintype "passive"))
      (node (ref "U1") (pin "P$C1") (pinfunction "DEC1_P$C1") (pintype "power_in"))
    )
    (net (code "4") (name "DEC3") (class "Default")
      (node (ref "C11") (pin "1") (pinfunction "1_1") (pintype "passive"))
      (node (ref "U1") (pin "P$D23") (pinfunction "DEC3_P$D23") (pintype "bidirectional"))
    )
    (net (code "5") (name "DEC4_6") (class "Default")
      (node (ref "C10") (pin "1") (pinfunction "1_1") (pintype "passive"))
      (node (ref "C15") (pin "1") (pinfunction "1_1") (pintype "passive"))
      (node (ref "C16") (pin "1") (pinfunction "1_1") (pintype "passive"))
      (node (ref "L3") (pin "2") (pinfunction "2_2") (pintype "passive"))
      (node (ref "U1") (pin "P$B5") (pinfunction "DEC4_P$B5") (pintype "power_in"))
      (node (ref "U1") (pin "P$E24") (pinfunction "DEC6_P$E24") (pintype "bidirectional"))
    )
    (net (code "6") (name "DN") (class "Default")
      (node (ref "D3") (pin "1") (pinfunction "I/O1_1_1") (pintype "bidirectional"))
      (node (ref "J4") (pin "A7") (pinfunction "DN1_A7") (pintype "bidirectional"))
      (node (ref "J4") (pin "B7") (pinfunction "DN2_B7") (pintype "bidirectional"))
    )
    (net (code "7") (name "DP") (class "Default")
      (node (ref "D3") (pin "3") (pinfunction "I/O2_1_3") (pintype "bidirectional"))
      (node (ref "J4") (pin "A6") (pinfunction "DP1_A6") (pintype "bidirectional"))
      (node (ref "J4") (pin "B6") (pinfunction "DP2_B6") (pintype "bidirectional"))
    )
    (net (code "8") (name "D_N") (class "Default")
      (node (ref "D3") (pin "4") (pinfunction "I/O2_2_4") (pintype "bidirectional"))
      (node (ref "U1") (pin "P$AD4") (pinfunction "D-_P$AD4") (pintype "bidirectional"))
    )
    (net (code "9") (name "D_P") (class "Default")
      (node (ref "D3") (pin "6") (pinfunction "I/O1_2_6") (pintype "bidirectional"))
      (node (ref "U1") (pin "P$AD6") (pinfunction "D+_P$AD6") (pintype "bidirectional"))
    )
    (net (code "10") (name "EPD_3V3") (class "Default")
      (node (ref "C1-EP-DR") (pin "1") (pinfunction "1_1") (pintype "passive"))
      (node (ref "EPD_C5") (pin "2") (pinfunction "2_2") (pintype "passive"))
      (node (ref "J1") (pin "15") (pinfunction "15_15") (pintype "bidirectional"))
      (node (ref "J1") (pin "16") (pinfunction "16_16") (pintype "bidirectional"))
      (node (ref "L5") (pin "2") (pinfunction "2_2") (pintype "passive"))
      (node (ref "Q1") (pin "3") (pinfunction "D_3") (pintype "bidirectional"))
    )
    (net (code "11") (name "EPD_BUSY") (class "Default")
      (node (ref "J1") (pin "9") (pinfunction "9_9") (pintype "bidirectional"))
      (node (ref "U1") (pin "P$AD12") (pinfunction "P0.17_P$AD12") (pintype "bidirectional"))
    )
    (net (code "12") (name "EPD_CS") (class "Default")
      (node (ref "J1") (pin "12") (pinfunction "12_12") (pintype "bidirectional"))
      (node (ref "U1") (pin "P$K2") (pinfunction "P0.05/AIN3_P$K2") (pintype "bidirectional"))
    )
    (net (code "13") (name "EPD_DC") (class "Default")
      (node (ref "J1") (pin "11") (pinfunction "11_11") (pintype "bidirectional"))
      (node (ref "U1") (pin "P$AD10") (pinfunction "P0.15_P$AD10") (pintype "bidirectional"))
    )
    (net (code "14") (name "EPD_RST") (class "Default")
      (node (ref "J1") (pin "10") (pinfunction "10_10") (pintype "bidirectional"))
      (node (ref "U1") (pin "P$AC11") (pinfunction "P0.16_P$AC11") (pintype "bidirectional"))
    )
    (net (code "15") (name "GDR") (class "Default")
      (node (ref "J1") (pin "2") (pinfunction "2_2") (pintype "bidirectional"))
      (node (ref "Q3") (pin "1") (pinfunction "G_1") (pintype "bidirectional"))
      (node (ref "R2_EP_DR") (pin "2") (pinfunction "2_2") (pintype "bidirectional"))
    )
    (net (code "16") (name "GND") (class "Default")
      (node (ref "C1") (pin "2") (pinfunction "2_2") (pintype "passive"))
      (node (ref "C1-EP-DR") (pin "2") (pinfunction "2_2") (pintype "passive"))
      (node (ref "C10") (pin "2") (pinfunction "2_2") (pintype "passive"))
      (node (ref "C11") (pin "2") (pinfunction "2_2") (pintype "passive"))
      (node (ref "C12") (pin "2") (pinfunction "2_2") (pintype "passive"))
      (node (ref "C13") (pin "2") (pinfunction "2_2") (pintype "passive"))
      (node (ref "C14") (pin "2") (pinfunction "2_2") (pintype "passive"))
      (node (ref "C15") (pin "2") (pinfunction "2_2") (pintype "passive"))
      (node (ref "C16") (pin "2") (pinfunction "2_2") (pintype "passive"))
      (node (ref "C17") (pin "1") (pinfunction "1_1") (pintype "passive"))
      (node (ref "C18") (pin "1") (pinfunction "1_1") (pintype "passive"))
      (node (ref "C19") (pin "2") (pinfunction "2_2") (pintype "passive"))
      (node (ref "C2") (pin "2") (pinfunction "2_2") (pintype "passive"))
      (node (ref "C20") (pin "2") (pinfunction "2_2") (pintype "passive"))
      (node (ref "C21") (pin "2") (pinfunction "2_2") (pintype "passive"))
      (node (ref "C22") (pin "2") (pinfunction "2_2") (pintype "passive"))
      (node (ref "C23") (pin "1") (pinfunction "1_1") (pintype "passive"))
      (node (ref "C24") (pin "1") (pinfunction "1_1") (pintype "passive"))
      (node (ref "C25") (pin "2") (pinfunction "2_2") (pintype "passive"))
      (node (ref "C27") (pin "2") (pinfunction "2_2") (pintype "passive"))
      (node (ref "C29") (pin "2") (pinfunction "2_2") (pintype "passive"))
      (node (ref "C3") (pin "2") (pinfunction "2_2") (pintype "passive"))
      (node (ref "C30") (pin "2") (pinfunction "2_2") (pintype "passive"))
      (node (ref "C31") (pin "2") (pinfunction "2_2") (pintype "passive"))
      (node (ref "C32") (pin "2") (pinfunction "2_2") (pintype "passive"))
      (node (ref "C33") (pin "2") (pinfunction "2_2") (pintype "passive"))
      (node (ref "C34") (pin "2") (pinfunction "2_2") (pintype "passive"))
      (node (ref "C37") (pin "2") (pinfunction "2_2") (pintype "passive"))
      (node (ref "C38") (pin "2") (pinfunction "2_2") (pintype "passive"))
      (node (ref "C39") (pin "2") (pinfunction "2_2") (pintype "passive"))
      (node (ref "C4") (pin "2") (pinfunction "2_2") (pintype "passive"))
      (node (ref "C42") (pin "2") (pinfunction "2_2") (pintype "passive"))
      (node (ref "C43") (pin "2") (pinfunction "2_2") (pintype "passive"))
      (node (ref "C5") (pin "2") (pinfunction "2_2") (pintype "passive"))
      (node (ref "C6") (pin "2") (pinfunction "2_2") (pintype "passive"))
      (node (ref "C7") (pin "2") (pinfunction "2_2") (pintype "passive"))
      (node (ref "C8") (pin "2") (pinfunction "2_2") (pintype "passive"))
      (node (ref "C9") (pin "2") (pinfunction "2_2") (pintype "passive"))
      (node (ref "D3") (pin "2") (pinfunction "GND_2") (pintype "bidirectional"))
      (node (ref "D4") (pin "1") (pinfunction "K_1") (pintype "bidirectional"))
      (node (ref "EPD_C1") (pin "1") (pinfunction "1_1") (pintype "passive"))
      (node (ref "EPD_C10") (pin "1") (pinfunction "1_1") (pintype "passive"))
      (node (ref "EPD_C11") (pin "1") (pinfunction "1_1") (pintype "passive"))
      (node (ref "EPD_C12") (pin "1") (pinfunction "1_1") (pintype "passive"))
      (node (ref "EPD_C2") (pin "1") (pinfunction "1_1") (pintype "passive"))
      (node (ref "EPD_C5") (pin "1") (pinfunction "1_1") (pintype "passive"))
      (node (ref "EPD_C6") (pin "1") (pinfunction "1_1") (pintype "passive"))
      (node (ref "EPD_C7") (pin "1") (pinfunction "1_1") (pintype "passive"))
      (node (ref "EPD_C8") (pin "1") (pinfunction "1_1") (pintype "passive"))
      (node (ref "EPD_C9") (pin "1") (pinfunction "1_1") (pintype "passive"))
      (node (ref "IC1") (pin "D2") (pinfunction "GND_D2") (pintype "bidirectional"))
      (node (ref "IC2") (pin "B1") (pinfunction "IN/TRIG_B1") (pintype "bidirectional"))
      (node (ref "IC2") (pin "B3") (pinfunction "GND_B3") (pintype "bidirectional"))
      (node (ref "IC3") (pin "8") (pinfunction "GNDIO_8") (pintype "bidirectional"))
      (node (ref "IC3") (pin "9") (pinfunction "GND_9") (pintype "bidirectional"))
      (node (ref "IC9") (pin "B1") (pinfunction "VSEL_B1") (pintype "bidirectional"))
      (node (ref "IC9") (pin "C1") (pinfunction "AGND_C1") (pintype "bidirectional"))
      (node (ref "IC9") (pin "C2") (pinfunction "PGND_1_C2") (pintype "bidirectional"))
      (node (ref "IC9") (pin "C3") (pinfunction "PGND_2_C3") (pintype "bidirectional"))
      (node (ref "J1") (pin "17") (pinfunction "17_17") (pintype "bidirectional"))
      (node (ref "J1") (pin "8") (pinfunction "8_8") (pintype "bidirectional"))
      (node (ref "J1") (pin "MP1") (pinfunction "MP1_MP1") (pintype "bidirectional"))
      (node (ref "J1") (pin "MP2") (pinfunction "MP2_MP2") (pintype "bidirectional"))
      (node (ref "J2") (pin "3") (pinfunction "3_3") (pintype "bidirectional"))
      (node (ref "J2") (pin "5") (pinfunction "5_5") (pintype "bidirectional"))
      (node (ref "J4") (pin "A12_B1") (pinfunction "GND_A12_B1") (pintype "power_in"))
      (node (ref "J4") (pin "A1_B12") (pinfunction "GND_A1_B12") (pintype "power_in"))
      (node (ref "J4") (pin "SH1") (pinfunction "SHIELD_SH1") (pintype "passive"))
      (node (ref "J4") (pin "SH2") (pinfunction "SHIELD_SH2") (pintype "passive"))
      (node (ref "J4") (pin "SH3") (pinfunction "SHIELD_SH3") (pintype "passive"))
      (node (ref "J4") (pin "SH4") (pinfunction "SHIELD_SH4") (pintype "passive"))
      (node (ref "R1_USB") (pin "1") (pinfunction "1_1") (pintype "bidirectional"))
      (node (ref "R2_EP_DR") (pin "1") (pinfunction "1_1") (pintype "bidirectional"))
      (node (ref "R2_USB") (pin "2") (pinfunction "2_2") (pintype "bidirectional"))
      (node (ref "R3") (pin "2") (pinfunction "2_2") (pintype "bidirectional"))
      (node (ref "R9") (pin "1") (pinfunction "1_1") (pintype "bidirectional"))
      (node (ref "R_TYPE_SEL") (pin "1") (pinfunction "1_1") (pintype "bidirectional"))
      (node (ref "SJ1") (pin "1") (pinfunction "1_1") (pintype "passive"))
      (node (ref "SW_DN") (pin "1") (pinfunction "1_1") (pintype "passive"))
      (node (ref "SW_ENT") (pin "1") (pinfunction "1_1") (pintype "passive"))
      (node (ref "SW_UP") (pin "1") (pinfunction "1_1") (pintype "passive"))
      (node (ref "TP_BAT_GND") (pin "TP") (pinfunction "TP_TP") (pintype "input"))
      (node (ref "TP_GND") (pin "TP") (pinfunction "TP_TP") (pintype "input"))
      (node (ref "U1") (pin "P$74") (pinfunction "VSS_PAD_P$74") (pintype "bidirectional"))
      (node (ref "U1") (pin "P$75") (pinfunction "VSS_PAD_P$75") (pintype "bidirectional"))
      (node (ref "U1") (pin "P$76") (pinfunction "VSS_PAD_P$76") (pintype "bidirectional"))
      (node (ref "U1") (pin "P$77") (pinfunction "VSS_PAD_P$77") (pintype "bidirectional"))
      (node (ref "U1") (pin "P$78") (pinfunction "VSS_PAD_P$78") (pintype "bidirectional"))
      (node (ref "U1") (pin "P$79") (pinfunction "VSS_PAD_P$79") (pintype "bidirectional"))
      (node (ref "U1") (pin "P$80") (pinfunction "VSS_PAD_P$80") (pintype "bidirectional"))
      (node (ref "U1") (pin "P$81") (pinfunction "VSS_PAD_P$81") (pintype "bidirectional"))
      (node (ref "U1") (pin "P$82") (pinfunction "VSS_PAD_P$82") (pintype "bidirectional"))
      (node (ref "U1") (pin "P$83") (pinfunction "VSS_PAD_P$83") (pintype "bidirectional"))
      (node (ref "U1") (pin "P$84") (pinfunction "VSS_PAD_P$84") (pintype "bidirectional"))
      (node (ref "U1") (pin "P$85") (pinfunction "VSS_PAD_P$85") (pintype "bidirectional"))
      (node (ref "U1") (pin "P$86") (pinfunction "VSS_PAD_P$86") (pintype "bidirectional"))
      (node (ref "U1") (pin "P$87") (pinfunction "VSS_PAD_P$87") (pintype "bidirectional"))
      (node (ref "U1") (pin "P$88") (pinfunction "VSS_PAD_P$88") (pintype "bidirectional"))
      (node (ref "U1") (pin "P$89") (pinfunction "VSS_PAD_P$89") (pintype "bidirectional"))
      (node (ref "U1") (pin "P$90") (pinfunction "VSS_PAD_P$90") (pintype "bidirectional"))
      (node (ref "U1") (pin "P$B7") (pinfunction "VSS_P$B7") (pintype "power_in"))
      (node (ref "U1") (pin "P$F23") (pinfunction "VSS_PA_P$F23") (pintype "bidirectional"))
      (node (ref "U3") (pin "1") (pinfunction "CTG_1") (pintype "power_in"))
      (node (ref "U3") (pin "4") (pinfunction "GND_4") (pintype "power_in"))
      (node (ref "U3") (pin "6") (pinfunction "QSTRT_6") (pintype "input"))
      (node (ref "U3") (pin "9") (pinfunction "EP_9") (pintype "power_in"))
      (node (ref "X1") (pin "2") (pinfunction "2_2") (pintype "passive"))
      (node (ref "X1") (pin "4") (pinfunction "4_4") (pintype "passive"))
    )
    (net (code "17") (name "HAPTIC_EN") (class "Default")
      (node (ref "IC2") (pin "A1") (pinfunction "EN_A1") (pintype "bidirectional"))
      (node (ref "U1") (pin "P$U1") (pinfunction "P0.12_P$U1") (pintype "bidirectional"))
    )
    (net (code "18") (name "IMU_INT1") (class "Default")
      (node (ref "IC3") (pin "5") (pinfunction "INT1_5") (pintype "bidirectional"))
      (node (ref "U1") (pin "P$N1") (pinfunction "P0.08_P$N1") (pintype "bidirectional"))
    )
    (net (code "19") (name "IMU_INT2") (class "Default")
      (node (ref "IC3") (pin "6") (pinfunction "INT2_6") (pintype "bidirectional"))
      (node (ref "U1") (pin "P$P2") (pinfunction "P1.08_P$P2") (pintype "bidirectional"))
    )
    (net (code "20") (name "LX1") (class "Default")
      (node (ref "IC9") (pin "B2") (pinfunction "SW1_1_B2") (pintype "bidirectional"))
      (node (ref "IC9") (pin "B3") (pinfunction "SW1_2_B3") (pintype "bidirectional"))
      (node (ref "L7") (pin "1") (pinfunction "1_1") (pintype "bidirectional"))
    )
    (net (code "21") (name "LX2") (class "Default")
      (node (ref "IC9") (pin "D2") (pinfunction "SW2_1_D2") (pintype "bidirectional"))
      (node (ref "IC9") (pin "D3") (pinfunction "SW2_2_D3") (pintype "bidirectional"))
      (node (ref "L7") (pin "2") (pinfunction "2_2") (pintype "bidirectional"))
    )
    (net (code "22") (name "MOSI") (class "Default")
      (node (ref "J1") (pin "14") (pinfunction "14_14") (pintype "bidirectional"))
      (node (ref "U1") (pin "P$B13") (pinfunction "P0.03/AIN1_P$B13") (pintype "bidirectional"))
    )
    (net (code "23") (name "Net-(ANT1-FEED)") (class "Default")
      (node (ref "ANT1") (pin "1") (pinfunction "FEED_1") (pintype "input"))
      (node (ref "C22") (pin "1") (pinfunction "1_1") (pintype "passive"))
      (node (ref "C4") (pin "1") (pinfunction "1_1") (pintype "passive"))
      (node (ref "L1") (pin "2") (pinfunction "2_2") (pintype "passive"))
    )
    (net (code "24") (name "Net-(D2-K)") (class "Default")
      (node (ref "C2-EP-DR") (pin "1") (pinfunction "1_1") (pintype "passive"))
      (node (ref "D2") (pin "1") (pinfunction "K_1") (pintype "bidirectional"))
      (node (ref "D4") (pin "2") (pinfunction "A_2") (pintype "bidirectional"))
    )
    (net (code "25") (name "Net-(D5-A)") (class "Default")
      (node (ref "C2-EP-DR") (pin "2") (pinfunction "2_2") (pintype "passive"))
      (node (ref "D5") (pin "2") (pinfunction "A_2") (pintype "bidirectional"))
      (node (ref "L5") (pin "1") (pinfunction "1_1") (pintype "passive"))
      (node (ref "Q3") (pin "3") (pinfunction "D_3") (pintype "bidirectional"))
    )
    (net (code "26") (name "Net-(EPD_C1-Pad2)") (class "Default")
      (node (ref "EPD_C1") (pin "2") (pinfunction "2_2") (pintype "passive"))
      (node (ref "J1") (pin "5") (pinfunction "5_5") (pintype "bidirectional"))
    )
    (net (code "27") (name "Net-(EPD_C2-Pad2)") (class "Default")
      (node (ref "EPD_C2") (pin "2") (pinfunction "2_2") (pintype "passive"))
      (node (ref "J1") (pin "4") (pinfunction "4_4") (pintype "bidirectional"))
    )
    (net (code "28") (name "Net-(EPD_C6-Pad2)") (class "Default")
      (node (ref "EPD_C6") (pin "2") (pinfunction "2_2") (pintype "passive"))
      (node (ref "J1") (pin "18") (pinfunction "18_18") (pintype "bidirectional"))
    )
    (net (code "29") (name "Net-(EPD_C7-Pad2)") (class "Default")
      (node (ref "EPD_C7") (pin "2") (pinfunction "2_2") (pintype "passive"))
      (node (ref "J1") (pin "19") (pinfunction "19_19") (pintype "bidirectional"))
    )
    (net (code "30") (name "Net-(EPD_C8-Pad2)") (class "Default")
      (node (ref "EPD_C8") (pin "2") (pinfunction "2_2") (pintype "passive"))
      (node (ref "J1") (pin "20") (pinfunction "20_20") (pintype "bidirectional"))
    )
    (net (code "31") (name "Net-(EPD_C10-Pad2)") (class "Default")
      (node (ref "EPD_C10") (pin "2") (pinfunction "2_2") (pintype "passive"))
      (node (ref "J1") (pin "22") (pinfunction "22_22") (pintype "bidirectional"))
    )
    (net (code "32") (name "Net-(EPD_C12-Pad2)") (class "Default")
      (node (ref "EPD_C12") (pin "2") (pinfunction "2_2") (pintype "passive"))
      (node (ref "J1") (pin "24") (pinfunction "24_24") (pintype "bidirectional"))
    )
    (net (code "33") (name "Net-(IC1-TS{slash}MR)") (class "Default")
      (node (ref "IC1") (pin "D1") (pinfunction "TS/MR_D1") (pintype "bidirectional"))
      (node (ref "R9") (pin "2") (pinfunction "2_2") (pintype "bidirectional"))
    )
    (net (code "34") (name "Net-(IC2-REG)") (class "Default")
      (node (ref "C32") (pin "1") (pinfunction "1_1") (pintype "passive"))
      (node (ref "IC2") (pin "A2") (pinfunction "REG_A2") (pintype "bidirectional"))
    )
    (net (code "35") (name "Net-(IC3-SDO)") (class "Default")
      (node (ref "IC3") (pin "1") (pinfunction "SDO_1") (pintype "bidirectional"))
      (node (ref "R3") (pin "1") (pinfunction "1_1") (pintype "bidirectional"))
    )
    (net (code "36") (name "Net-(IC9-SCL)") (class "Default")
      (node (ref "IC9") (pin "D1") (pinfunction "SCL_D1") (pintype "bidirectional"))
      (node (ref "R4") (pin "1") (pinfunction "1_1") (pintype "bidirectional"))
    )
    (net (code "37") (name "Net-(IC9-SDA)") (class "Default")
      (node (ref "IC9") (pin "E1") (pinfunction "SDA_E1") (pintype "bidirectional"))
      (node (ref "R2") (pin "1") (pinfunction "1_1") (pintype "bidirectional"))
    )
    (net (code "38") (name "Net-(J4-CC1)") (class "Default")
      (node (ref "J4") (pin "A5") (pinfunction "CC1_A5") (pintype "bidirectional"))
      (node (ref "R1_USB") (pin "2") (pinfunction "2_2") (pintype "bidirectional"))
    )
    (net (code "39") (name "Net-(J4-CC2)") (class "Default")
      (node (ref "J4") (pin "B5") (pinfunction "CC2_B5") (pintype "bidirectional"))
      (node (ref "R2_USB") (pin "1") (pinfunction "1_1") (pintype "bidirectional"))
    )
    (net (code "40") (name "Net-(L2-Pad2)") (class "Default")
      (node (ref "L2") (pin "2") (pinfunction "2_2") (pintype "passive"))
      (node (ref "L3") (pin "1") (pinfunction "1_1") (pintype "passive"))
    )
    (net (code "41") (name "Net-(R1_EP_DR-Pad1)") (class "Default")
      (node (ref "R1_EP_DR") (pin "1") (pinfunction "1_1") (pintype "bidirectional"))
      (node (ref "R_TYPE_SEL") (pin "2") (pinfunction "2_2") (pintype "bidirectional"))
      (node (ref "SJ1") (pin "2") (pinfunction "2_2") (pintype "passive"))
    )
    (net (code "42") (name "Net-(U1-ANT)") (class "Default")
      (node (ref "C3") (pin "1") (pinfunction "1_1") (pintype "passive"))
      (node (ref "L1") (pin "1") (pinfunction "1_1") (pintype "passive"))
      (node (ref "U1") (pin "P$H23") (pinfunction "ANT_P$H23") (pintype "bidirectional"))
    )
    (net (code "43") (name "Net-(U1-DCC)") (class "Default")
      (node (ref "L2") (pin "1") (pinfunction "1_1") (pintype "passive"))
      (node (ref "U1") (pin "P$B3") (pinfunction "DCC_P$B3") (pintype "output"))
    )
    (net (code "44") (name "Net-(U1-DEC2)") (class "Default")
      (node (ref "C13") (pin "1") (pinfunction "1_1") (pintype "passive"))
      (node (ref "U1") (pin "P$A18") (pinfunction "DEC2_P$A18") (pintype "bidirectional"))
    )
    (net (code "45") (name "Net-(U1-DEC3V3)") (class "Default")
      (node (ref "C20") (pin "1") (pinfunction "1_1") (pintype "passive"))
      (node (ref "U1") (pin "P$AC5") (pinfunction "DEC3V3_P$AC5") (pintype "bidirectional"))
    )
    (net (code "46") (name "Net-(U1-DEC5)") (class "Default")
      (node (ref "C9") (pin "1") (pinfunction "1_1") (pintype "passive"))
      (node (ref "U1") (pin "P$N24") (pinfunction "DEC5_P$N24") (pintype "bidirectional"))
    )
    (net (code "47") (name "Net-(U1-XC1)") (class "Default")
      (node (ref "C1") (pin "1") (pinfunction "1_1") (pintype "passive"))
      (node (ref "U1") (pin "P$B24") (pinfunction "XC1_P$B24") (pintype "input"))
      (node (ref "X1") (pin "1") (pinfunction "1_1") (pintype "passive"))
    )
    (net (code "48") (name "Net-(U1-XC2)") (class "Default")
      (node (ref "C2") (pin "1") (pinfunction "1_1") (pintype "passive"))
      (node (ref "U1") (pin "P$A23") (pinfunction "XC2_P$A23") (pintype "output"))
      (node (ref "X1") (pin "3") (pinfunction "3_3") (pintype "passive"))
    )
    (net (code "49") (name "OUT+") (class "Default")
      (node (ref "IC2") (pin "A3") (pinfunction "OUT+_A3") (pintype "bidirectional"))
      (node (ref "TP_OP") (pin "TP") (pinfunction "TP_TP") (pintype "input"))
    )
    (net (code "50") (name "OUT-") (class "Default")
      (node (ref "IC2") (pin "C3") (pinfunction "OUT-_C3") (pintype "bidirectional"))
      (node (ref "TP_ON") (pin "TP") (pinfunction "TP_TP") (pintype "input"))
    )
    (net (code "51") (name "P0.00") (class "Default")
      (node (ref "C17") (pin "2") (pinfunction "2_2") (pintype "passive"))
      (node (ref "U1") (pin "P$D2") (pinfunction "P0.00/XL1_P$D2") (pintype "bidirectional"))
      (node (ref "X2") (pin "1") (pinfunction "1_1") (pintype "passive"))
    )
    (net (code "52") (name "P0.01") (class "Default")
      (node (ref "C18") (pin "2") (pinfunction "2_2") (pintype "passive"))
      (node (ref "U1") (pin "P$F2") (pinfunction "P0.01/XL2_P$F2") (pintype "bidirectional"))
      (node (ref "X2") (pin "2") (pinfunction "2_2") (pintype "passive"))
    )
    (net (code "53") (name "P0.04") (class "Default")
      (node (ref "U1") (pin "P$J1") (pinfunction "P0.04/AIN2_P$J1") (pintype "bidirectional"))
    )
    (net (code "54") (name "P0.09") (class "Default")
      (node (ref "U1") (pin "P$L24") (pinfunction "P0.09/NFC1_P$L24") (pintype "bidirectional"))
    )
    (net (code "55") (name "P0.13") (class "Default")
      (node (ref "C30") (pin "1") (pinfunction "1_1") (pintype "passive"))
      (node (ref "R5") (pin "1") (pinfunction "1_1") (pintype "bidirectional"))
      (node (ref "SW_UP") (pin "2") (pinfunction "2_2") (pintype "passive"))
      (node (ref "U1") (pin "P$AD8") (pinfunction "P0.13_P$AD8") (pintype "bidirectional"))
    )
    (net (code "56") (name "P0.14") (class "Default")
      (node (ref "C31") (pin "1") (pinfunction "1_1") (pintype "passive"))
      (node (ref "R8") (pin "1") (pinfunction "1_1") (pintype "bidirectional"))
      (node (ref "SW_ENT") (pin "2") (pinfunction "2_2") (pintype "passive"))
      (node (ref "U1") (pin "P$AC9") (pinfunction "P0.14_P$AC9") (pintype "bidirectional"))
    )
    (net (code "57") (name "P0.19") (class "Default")
      (node (ref "U1") (pin "P$AC15") (pinfunction "P0.19_P$AC15") (pintype "bidirectional"))
    )
    (net (code "58") (name "P0.20") (class "Default")
      (node (ref "U1") (pin "P$AD16") (pinfunction "P0.20_P$AD16") (pintype "bidirectional"))
    )
    (net (code "59") (name "P0.21") (class "Default")
      (node (ref "U1") (pin "P$AC17") (pinfunction "P0.21_P$AC17") (pintype "bidirectional"))
    )
    (net (code "60") (name "P0.22") (class "Default")
      (node (ref "U1") (pin "P$AD18") (pinfunction "P0.22_P$AD18") (pintype "bidirectional"))
    )
    (net (code "61") (name "P0.23") (class "Default")
      (node (ref "U1") (pin "P$AC19") (pinfunction "P0.23_P$AC19") (pintype "bidirectional"))
    )
    (net (code "62") (name "P0.24") (class "Default")
      (node (ref "U1") (pin "P$AD20") (pinfunction "P0.24_P$AD20") (pintype "bidirectional"))
    )
    (net (code "63") (name "P0.25") (class "Default")
      (node (ref "U1") (pin "P$AC21") (pinfunction "P0.25_P$AC21") (pintype "bidirectional"))
    )
    (net (code "64") (name "P0.26") (class "Default")
      (node (ref "U1") (pin "P$G1") (pinfunction "P0.26_P$G1") (pintype "bidirectional"))
    )
    (net (code "65") (name "P0.27") (class "Default")
      (node (ref "U1") (pin "P$H2") (pinfunction "P0.27_P$H2") (pintype "bidirectional"))
    )
    (net (code "66") (name "P0.28") (class "Default")
      (node (ref "U1") (pin "P$B11") (pinfunction "P0.28/AIN4_P$B11") (pintype "bidirectional"))
    )
    (net (code "67") (name "P0.29") (class "Default")
      (node (ref "U1") (pin "P$A10") (pinfunction "P0.29/AIN5_P$A10") (pintype "bidirectional"))
    )
    (net (code "68") (name "P0.30") (class "Default")
      (node (ref "U1") (pin "P$B9") (pinfunction "P0.30/AIN6_P$B9") (pintype "bidirectional"))
    )
    (net (code "69") (name "P0.31") (class "Default")
      (node (ref "U1") (pin "P$A8") (pinfunction "P0.31/AIN7_P$A8") (pintype "bidirectional"))
    )
    (net (code "70") (name "P1.01") (class "Default")
      (node (ref "Q1") (pin "1") (pinfunction "G_1") (pintype "bidirectional"))
      (node (ref "R_PWR_EPD") (pin "1") (pinfunction "1_1") (pintype "bidirectional"))
      (node (ref "U1") (pin "P$Y23") (pinfunction "P1.01_P$Y23") (pintype "bidirectional"))
    )
    (net (code "71") (name "P1.02") (class "Default")
      (node (ref "C29") (pin "1") (pinfunction "1_1") (pintype "passive"))
      (node (ref "R7") (pin "1") (pinfunction "1_1") (pintype "bidirectional"))
      (node (ref "SW_DN") (pin "2") (pinfunction "2_2") (pintype "passive"))
      (node (ref "U1") (pin "P$W24") (pinfunction "P1.02_P$W24") (pintype "bidirectional"))
    )
    (net (code "72") (name "P1.03") (class "Default")
      (node (ref "U1") (pin "P$V23") (pinfunction "P1.03_P$V23") (pintype "bidirectional"))
    )
    (net (code "73") (name "P1.04") (class "Default")
      (node (ref "U1") (pin "P$U24") (pinfunction "P1.04_P$U24") (pintype "bidirectional"))
    )
    (net (code "74") (name "P1.05") (class "Default")
      (node (ref "U1") (pin "P$T23") (pinfunction "P1.05_P$T23") (pintype "bidirectional"))
    )
    (net (code "75") (name "P1.06") (class "Default")
      (node (ref "U1") (pin "P$R24") (pinfunction "P1.06_P$R24") (pintype "bidirectional"))
    )
    (net (code "76") (name "P1.07") (class "Default")
      (node (ref "U1") (pin "P$P23") (pinfunction "P1.07_P$P23") (pintype "bidirectional"))
    )
    (net (code "77") (name "P1.09") (class "Default")
      (node (ref "U1") (pin "P$R1") (pinfunction "P1.09_P$R1") (pintype "bidirectional"))
    )
    (net (code "78") (name "P1.10") (class "Default")
      (node (ref "U1") (pin "P$A20") (pinfunction "P1.10_P$A20") (pintype "bidirectional"))
    )
    (net (code "79") (name "P1.11") (class "Default")
      (node (ref "U1") (pin "P$B19") (pinfunction "P1.11_P$B19") (pintype "bidirectional"))
    )
    (net (code "80") (name "P1.12") (class "Default")
      (node (ref "U1") (pin "P$B17") (pinfunction "P1.12_P$B17") (pintype "bidirectional"))
    )
    (net (code "81") (name "P1.13") (class "Default")
      (node (ref "U1") (pin "P$A16") (pinfunction "P1.13_P$A16") (pintype "bidirectional"))
    )
    (net (code "82") (name "P1.14") (class "Default")
      (node (ref "U1") (pin "P$B15") (pinfunction "P1.14_P$B15") (pintype "bidirectional"))
    )
    (net (code "83") (name "P1.15") (class "Default")
      (node (ref "U1") (pin "P$A14") (pinfunction "P1.15_P$A14") (pintype "bidirectional"))
    )
    (net (code "84") (name "PMIC_INT") (class "Default")
      (node (ref "IC1") (pin "A1") (pinfunction "~{INT}_A1") (pintype "bidirectional"))
      (node (ref "U1") (pin "P$T2") (pinfunction "P0.11_P$T2") (pintype "bidirectional"))
    )
    (net (code "85") (name "PREVGH") (class "Default")
      (node (ref "D5") (pin "1") (pinfunction "K_1") (pintype "bidirectional"))
      (node (ref "EPD_C9") (pin "2") (pinfunction "2_2") (pintype "passive"))
      (node (ref "J1") (pin "21") (pinfunction "21_21") (pintype "bidirectional"))
    )
    (net (code "86") (name "PREVGL") (class "Default")
      (node (ref "D2") (pin "2") (pinfunction "A_2") (pintype "bidirectional"))
      (node (ref "EPD_C11") (pin "2") (pinfunction "2_2") (pintype "passive"))
      (node (ref "J1") (pin "23") (pinfunction "23_23") (pintype "bidirectional"))
    )
    (net (code "87") (name "RESE") (class "Default")
      (node (ref "J1") (pin "3") (pinfunction "3_3") (pintype "bidirectional"))
      (node (ref "Q3") (pin "2") (pinfunction "S_2") (pintype "bidirectional"))
      (node (ref "R1_EP_DR") (pin "2") (pinfunction "2_2") (pintype "bidirectional"))
    )
    (net (code "88") (name "RESET") (class "Default")
      (node (ref "J2") (pin "6") (pinfunction "6_6") (pintype "bidirectional"))
      (node (ref "TP_RESET") (pin "TP") (pinfunction "TP_TP") (pintype "input"))
      (node (ref "U1") (pin "P$AC13") (pinfunction "P0.18/RESET_P$AC13") (pintype "bidirectional"))
    )
    (net (code "89") (name "SCK") (class "Default")
      (node (ref "J1") (pin "13") (pinfunction "13_13") (pintype "bidirectional"))
      (node (ref "U1") (pin "P$A12") (pinfunction "P0.02/AIN0_P$A12") (pintype "bidirectional"))
    )
    (net (code "90") (name "SCL") (class "Default")
      (node (ref "IC1") (pin "B1") (pinfunction "SCL_B1") (pintype "bidirectional"))
      (node (ref "IC2") (pin "C1") (pinfunction "SCL_C1") (pintype "bidirectional"))
      (node (ref "IC3") (pin "12") (pinfunction "SCX_12") (pintype "bidirectional"))
      (node (ref "R17") (pin "2") (pinfunction "2_2") (pintype "bidirectional"))
      (node (ref "R4") (pin "2") (pinfunction "2_2") (pintype "bidirectional"))
      (node (ref "TP_SCL") (pin "TP") (pinfunction "TP_TP") (pintype "input"))
      (node (ref "U1") (pin "P$M2") (pinfunction "P0.07_P$M2") (pintype "bidirectional"))
      (node (ref "U3") (pin "7") (pinfunction "SCL_7") (pintype "input"))
    )
    (net (code "91") (name "SDA") (class "Default")
      (node (ref "IC1") (pin "C1") (pinfunction "SDA_C1") (pintype "bidirectional"))
      (node (ref "IC2") (pin "B2") (pinfunction "SDA_B2") (pintype "bidirectional"))
      (node (ref "IC3") (pin "2") (pinfunction "SDX_2") (pintype "bidirectional"))
      (node (ref "R18") (pin "2") (pinfunction "2_2") (pintype "bidirectional"))
      (node (ref "R2") (pin "2") (pinfunction "2_2") (pintype "bidirectional"))
      (node (ref "TP_SDA") (pin "TP") (pinfunction "TP_TP") (pintype "input"))
      (node (ref "U1") (pin "P$L1") (pinfunction "P0.06_P$L1") (pintype "bidirectional"))
      (node (ref "U3") (pin "8") (pinfunction "SDA_8") (pintype "bidirectional"))
    )
    (net (code "92") (name "SWDCLK") (class "Default")
      (node (ref "J2") (pin "4") (pinfunction "4_4") (pintype "bidirectional"))
      (node (ref "TP_SWDCLK") (pin "TP") (pinfunction "TP_TP") (pintype "input"))
      (node (ref "U1") (pin "P$AA24") (pinfunction "SWDCLK_P$AA24") (pintype "input"))
    )
    (net (code "93") (name "SWDIO") (class "Default")
      (node (ref "J2") (pin "2") (pinfunction "2_2") (pintype "bidirectional"))
      (node (ref "TP_SWDIO") (pin "TP") (pinfunction "TP_TP") (pintype "input"))
      (node (ref "U1") (pin "P$AC24") (pinfunction "SWDIO_P$AC24") (pintype "bidirectional"))
    )
    (net (code "94") (name "SWO") (class "Default")
      (node (ref "TP_SWO") (pin "TP") (pinfunction "TP_TP") (pintype "input"))
      (node (ref "U1") (pin "P$AD22") (pinfunction "P1.00_P$AD22") (pintype "bidirectional"))
    )
    (net (code "95") (name "VBAT") (class "Default")
      (node (ref "C27") (pin "1") (pinfunction "1_1") (pintype "passive"))
      (node (ref "C37") (pin "1") (pinfunction "1_1") (pintype "passive"))
      (node (ref "IC1") (pin "C2") (pinfunction "BAT_C2") (pintype "bidirectional"))
      (node (ref "TP_VBAT") (pin "TP") (pinfunction "TP_TP") (pintype "input"))
      (node (ref "U3") (pin "2") (pinfunction "CELL_2") (pintype "power_in"))
      (node (ref "U3") (pin "3") (pinfunction "VDD_3") (pintype "power_in"))
    )
    (net (code "96") (name "VBUS") (class "Default")
      (node (ref "C21") (pin "1") (pinfunction "1_1") (pintype "passive"))
      (node (ref "C38") (pin "1") (pinfunction "1_1") (pintype "passive"))
      (node (ref "C42") (pin "1") (pinfunction "1_1") (pintype "passive"))
      (node (ref "C43") (pin "1") (pinfunction "1_1") (pintype "passive"))
      (node (ref "D3") (pin "5") (pinfunction "VBUS_5") (pintype "bidirectional"))
      (node (ref "IC1") (pin "A2") (pinfunction "IN_A2") (pintype "bidirectional"))
      (node (ref "J4") (pin "A4_B9") (pinfunction "VBUS_A4_B9") (pintype "power_in"))
      (node (ref "J4") (pin "A9_B4") (pinfunction "VBUS_A9_B4") (pintype "power_in"))
      (node (ref "U1") (pin "P$AD2") (pinfunction "VBUS_P$AD2") (pintype "power_in"))
    )
    (net (code "97") (name "VREG") (class "Default")
      (node (ref "C23") (pin "2") (pinfunction "2_2") (pintype "passive"))
      (node (ref "C24") (pin "2") (pinfunction "2_2") (pintype "passive"))
      (node (ref "C39") (pin "1") (pinfunction "1_1") (pintype "passive"))
      (node (ref "IC1") (pin "B2") (pinfunction "SYS_B2") (pintype "bidirectional"))
      (node (ref "IC9") (pin "A1") (pinfunction "EN_A1") (pintype "bidirectional"))
      (node (ref "IC9") (pin "A2") (pinfunction "VIN_1_A2") (pintype "bidirectional"))
      (node (ref "IC9") (pin "A3") (pinfunction "VIN_2_A3") (pintype "bidirectional"))
      (node (ref "TP_VREG") (pin "TP") (pinfunction "TP_TP") (pintype "input"))
    )
    (net (code "98") (name "unconnected-(ANT1-NC-Pad2)") (class "Default")
      (node (ref "ANT1") (pin "2") (pinfunction "NC_2") (pintype "no_connect"))
    )
    (net (code "99") (name "unconnected-(IC3-ASCL-Pad11)") (class "Default")
      (node (ref "IC3") (pin "11") (pinfunction "ASCL_11") (pintype "bidirectional"))
    )
    (net (code "100") (name "unconnected-(IC3-ASDA-Pad4)") (class "Default")
      (node (ref "IC3") (pin "4") (pinfunction "ASDA_4") (pintype "bidirectional"))
    )
    (net (code "101") (name "unconnected-(J1-Pad1)") (class "Default")
      (node (ref "J1") (pin "1") (pinfunction "1_1") (pintype "bidirectional"))
    )
    (net (code "102") (name "unconnected-(J1-Pad6)") (class "Default")
      (node (ref "J1") (pin "6") (pinfunction "6_6") (pintype "bidirectional"))
    )
    (net (code "103") (name "unconnected-(J1-Pad7)") (class "Default")
      (node (ref "J1") (pin "7") (pinfunction "7_7") (pintype "bidirectional"))
    )
    (net (code "104") (name "unconnected-(J4-SBU1-PadA8)") (class "Default")
      (node (ref "J4") (pin "A8") (pinfunction "SBU1_A8") (pintype "bidirectional"))
    )
    (net (code "105") (name "unconnected-(J4-SBU2-PadB8)") (class "Default")
      (node (ref "J4") (pin "B8") (pinfunction "SBU2_B8") (pintype "bidirectional"))
    )
    (net (code "106") (name "unconnected-(U1-DCCH-PadP$AB2)") (class "Default")
      (node (ref "U1") (pin "P$AB2") (pinfunction "DCCH_P$AB2") (pintype "bidirectional"))
    )
  )
)
